# PulpPad.net
KiCad netlist of a schematic drawn in EAGLE
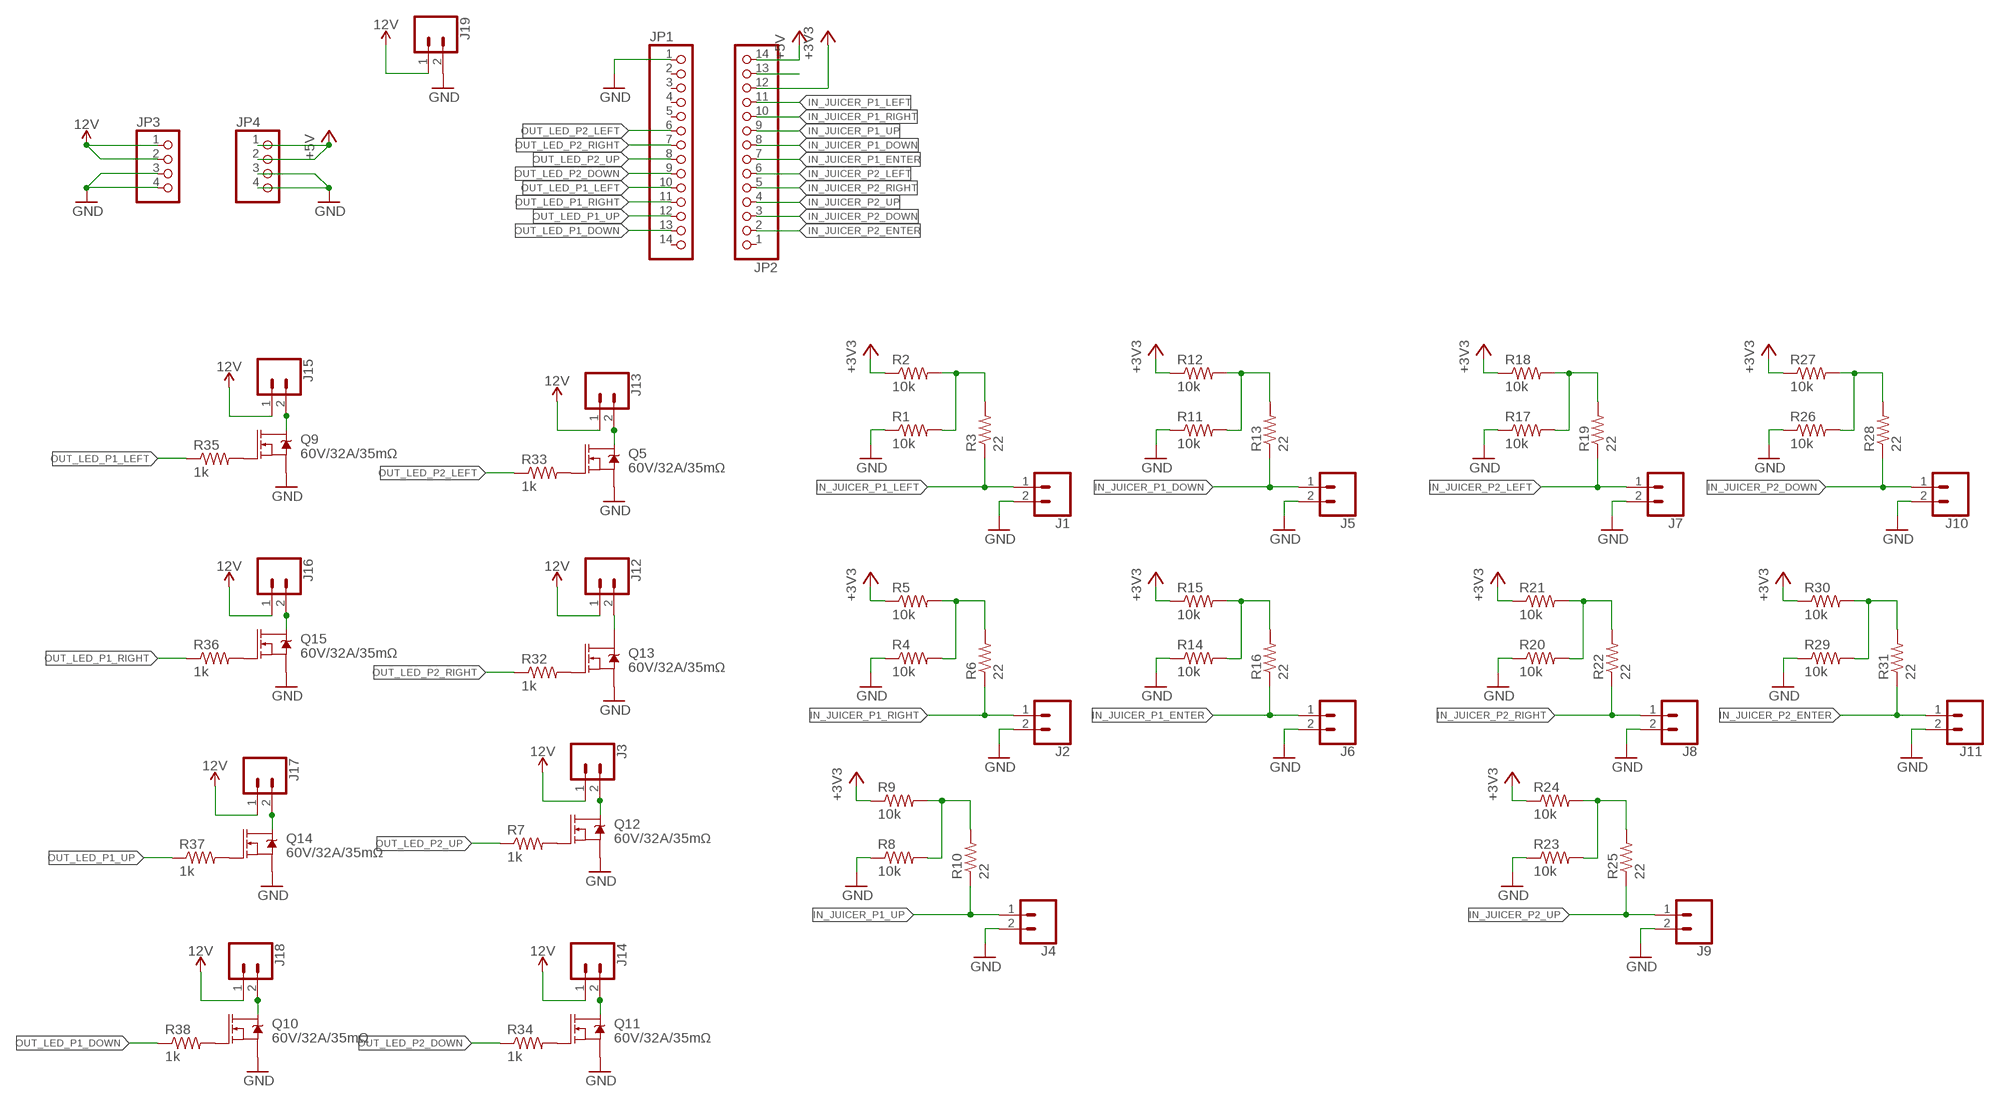
[diagram p0: schematic, sheet 1]

(export (version "E")
  (design (tool "Eeschema 10.0.6"))
  (components
    (comp (ref "J1")
      (value "CONN_023.5MM")
      (footprint "eagle-import:SCREWTERMINAL-3.5MM-2")
      (libsource (lib "eagle-import") (part "CONN_023.5MM"))
    )
    (comp (ref "J2")
      (value "CONN_023.5MM")
      (footprint "eagle-import:SCREWTERMINAL-3.5MM-2")
      (libsource (lib "eagle-import") (part "CONN_023.5MM"))
    )
    (comp (ref "J3")
      (value "CONN_023.5MM")
      (footprint "eagle-import:SCREWTERMINAL-3.5MM-2")
      (libsource (lib "eagle-import") (part "CONN_023.5MM"))
    )
    (comp (ref "J4")
      (value "CONN_023.5MM")
      (footprint "eagle-import:SCREWTERMINAL-3.5MM-2")
      (libsource (lib "eagle-import") (part "CONN_023.5MM"))
    )
    (comp (ref "J5")
      (value "CONN_023.5MM")
      (footprint "eagle-import:SCREWTERMINAL-3.5MM-2")
      (libsource (lib "eagle-import") (part "CONN_023.5MM"))
    )
    (comp (ref "J6")
      (value "CONN_023.5MM")
      (footprint "eagle-import:SCREWTERMINAL-3.5MM-2")
      (libsource (lib "eagle-import") (part "CONN_023.5MM"))
    )
    (comp (ref "J7")
      (value "CONN_023.5MM")
      (footprint "eagle-import:SCREWTERMINAL-3.5MM-2")
      (libsource (lib "eagle-import") (part "CONN_023.5MM"))
    )
    (comp (ref "J8")
      (value "CONN_023.5MM")
      (footprint "eagle-import:SCREWTERMINAL-3.5MM-2")
      (libsource (lib "eagle-import") (part "CONN_023.5MM"))
    )
    (comp (ref "J9")
      (value "CONN_023.5MM")
      (footprint "eagle-import:SCREWTERMINAL-3.5MM-2")
      (libsource (lib "eagle-import") (part "CONN_023.5MM"))
    )
    (comp (ref "J10")
      (value "CONN_023.5MM")
      (footprint "eagle-import:SCREWTERMINAL-3.5MM-2")
      (libsource (lib "eagle-import") (part "CONN_023.5MM"))
    )
    (comp (ref "J11")
      (value "CONN_023.5MM")
      (footprint "eagle-import:SCREWTERMINAL-3.5MM-2")
      (libsource (lib "eagle-import") (part "CONN_023.5MM"))
    )
    (comp (ref "J12")
      (value "CONN_023.5MM")
      (footprint "eagle-import:SCREWTERMINAL-3.5MM-2")
      (libsource (lib "eagle-import") (part "CONN_023.5MM"))
    )
    (comp (ref "J13")
      (value "CONN_023.5MM")
      (footprint "eagle-import:SCREWTERMINAL-3.5MM-2")
      (libsource (lib "eagle-import") (part "CONN_023.5MM"))
    )
    (comp (ref "J14")
      (value "CONN_023.5MM")
      (footprint "eagle-import:SCREWTERMINAL-3.5MM-2")
      (libsource (lib "eagle-import") (part "CONN_023.5MM"))
    )
    (comp (ref "J15")
      (value "CONN_023.5MM")
      (footprint "eagle-import:SCREWTERMINAL-3.5MM-2")
      (libsource (lib "eagle-import") (part "CONN_023.5MM"))
    )
    (comp (ref "J16")
      (value "CONN_023.5MM")
      (footprint "eagle-import:SCREWTERMINAL-3.5MM-2")
      (libsource (lib "eagle-import") (part "CONN_023.5MM"))
    )
    (comp (ref "J17")
      (value "CONN_023.5MM")
      (footprint "eagle-import:SCREWTERMINAL-3.5MM-2")
      (libsource (lib "eagle-import") (part "CONN_023.5MM"))
    )
    (comp (ref "J18")
      (value "CONN_023.5MM")
      (footprint "eagle-import:SCREWTERMINAL-3.5MM-2")
      (libsource (lib "eagle-import") (part "CONN_023.5MM"))
    )
    (comp (ref "J19")
      (value "CONN_023.5MM")
      (footprint "eagle-import:SCREWTERMINAL-3.5MM-2")
      (libsource (lib "eagle-import") (part "CONN_023.5MM"))
    )
    (comp (ref "JP1")
      (value "PINHD-1X14")
      (footprint "eagle-import:1X14")
      (libsource (lib "eagle-import") (part "PINHD-1X14"))
    )
    (comp (ref "JP2")
      (value "PINHD-1X14")
      (footprint "eagle-import:1X14")
      (libsource (lib "eagle-import") (part "PINHD-1X14"))
    )
    (comp (ref "JP3")
      (value "PINHD-1X4")
      (footprint "eagle-import:1X04")
      (libsource (lib "eagle-import") (part "PINHD-1X4"))
    )
    (comp (ref "JP4")
      (value "PINHD-1X4")
      (footprint "eagle-import:1X04")
      (libsource (lib "eagle-import") (part "PINHD-1X4"))
    )
    (comp (ref "Q5")
      (value "60V/32A/35mΩ")
      (footprint "eagle-import:TO220V")
      (libsource (lib "eagle-import") (part "MOSFET-NCH-FQP30N06L"))
    )
    (comp (ref "Q9")
      (value "60V/32A/35mΩ")
      (footprint "eagle-import:TO220V")
      (libsource (lib "eagle-import") (part "MOSFET-NCH-FQP30N06L"))
    )
    (comp (ref "Q10")
      (value "60V/32A/35mΩ")
      (footprint "eagle-import:TO220V")
      (libsource (lib "eagle-import") (part "MOSFET-NCH-FQP30N06L"))
    )
    (comp (ref "Q11")
      (value "60V/32A/35mΩ")
      (footprint "eagle-import:TO220V")
      (libsource (lib "eagle-import") (part "MOSFET-NCH-FQP30N06L"))
    )
    (comp (ref "Q12")
      (value "60V/32A/35mΩ")
      (footprint "eagle-import:TO220V")
      (libsource (lib "eagle-import") (part "MOSFET-NCH-FQP30N06L"))
    )
    (comp (ref "Q13")
      (value "60V/32A/35mΩ")
      (footprint "eagle-import:TO220V")
      (libsource (lib "eagle-import") (part "MOSFET-NCH-FQP30N06L"))
    )
    (comp (ref "Q14")
      (value "60V/32A/35mΩ")
      (footprint "eagle-import:TO220V")
      (libsource (lib "eagle-import") (part "MOSFET-NCH-FQP30N06L"))
    )
    (comp (ref "Q15")
      (value "60V/32A/35mΩ")
      (footprint "eagle-import:TO220V")
      (libsource (lib "eagle-import") (part "MOSFET-NCH-FQP30N06L"))
    )
    (comp (ref "R1")
      (value "10k")
      (footprint "eagle-import:0204_7")
      (libsource (lib "eagle-import") (part "R-US_0204/7"))
    )
    (comp (ref "R2")
      (value "10k")
      (footprint "eagle-import:0204_7")
      (libsource (lib "eagle-import") (part "R-US_0204/7"))
    )
    (comp (ref "R3")
      (value "22")
      (footprint "eagle-import:0204_7")
      (libsource (lib "eagle-import") (part "R-US_0204/7"))
    )
    (comp (ref "R4")
      (value "10k")
      (footprint "eagle-import:0204_7")
      (libsource (lib "eagle-import") (part "R-US_0204/7"))
    )
    (comp (ref "R5")
      (value "10k")
      (footprint "eagle-import:0204_7")
      (libsource (lib "eagle-import") (part "R-US_0204/7"))
    )
    (comp (ref "R6")
      (value "22")
      (footprint "eagle-import:0204_7")
      (libsource (lib "eagle-import") (part "R-US_0204/7"))
    )
    (comp (ref "R7")
      (value "1k")
      (footprint "eagle-import:0204_7")
      (libsource (lib "eagle-import") (part "R-US_0204/7"))
    )
    (comp (ref "R8")
      (value "10k")
      (footprint "eagle-import:0204_7")
      (libsource (lib "eagle-import") (part "R-US_0204/7"))
    )
    (comp (ref "R9")
      (value "10k")
      (footprint "eagle-import:0204_7")
      (libsource (lib "eagle-import") (part "R-US_0204/7"))
    )
    (comp (ref "R10")
      (value "22")
      (footprint "eagle-import:0204_7")
      (libsource (lib "eagle-import") (part "R-US_0204/7"))
    )
    (comp (ref "R11")
      (value "10k")
      (footprint "eagle-import:0204_7")
      (libsource (lib "eagle-import") (part "R-US_0204/7"))
    )
    (comp (ref "R12")
      (value "10k")
      (footprint "eagle-import:0204_7")
      (libsource (lib "eagle-import") (part "R-US_0204/7"))
    )
    (comp (ref "R13")
      (value "22")
      (footprint "eagle-import:0204_7")
      (libsource (lib "eagle-import") (part "R-US_0204/7"))
    )
    (comp (ref "R14")
      (value "10k")
      (footprint "eagle-import:0204_7")
      (libsource (lib "eagle-import") (part "R-US_0204/7"))
    )
    (comp (ref "R15")
      (value "10k")
      (footprint "eagle-import:0204_7")
      (libsource (lib "eagle-import") (part "R-US_0204/7"))
    )
    (comp (ref "R16")
      (value "22")
      (footprint "eagle-import:0204_7")
      (libsource (lib "eagle-import") (part "R-US_0204/7"))
    )
    (comp (ref "R17")
      (value "10k")
      (footprint "eagle-import:0204_7")
      (libsource (lib "eagle-import") (part "R-US_0204/7"))
    )
    (comp (ref "R18")
      (value "10k")
      (footprint "eagle-import:0204_7")
      (libsource (lib "eagle-import") (part "R-US_0204/7"))
    )
    (comp (ref "R19")
      (value "22")
      (footprint "eagle-import:0204_7")
      (libsource (lib "eagle-import") (part "R-US_0204/7"))
    )
    (comp (ref "R20")
      (value "10k")
      (footprint "eagle-import:0204_7")
      (libsource (lib "eagle-import") (part "R-US_0204/7"))
    )
    (comp (ref "R21")
      (value "10k")
      (footprint "eagle-import:0204_7")
      (libsource (lib "eagle-import") (part "R-US_0204/7"))
    )
    (comp (ref "R22")
      (value "22")
      (footprint "eagle-import:0204_7")
      (libsource (lib "eagle-import") (part "R-US_0204/7"))
    )
    (comp (ref "R23")
      (value "10k")
      (footprint "eagle-import:0204_7")
      (libsource (lib "eagle-import") (part "R-US_0204/7"))
    )
    (comp (ref "R24")
      (value "10k")
      (footprint "eagle-import:0204_7")
      (libsource (lib "eagle-import") (part "R-US_0204/7"))
    )
    (comp (ref "R25")
      (value "22")
      (footprint "eagle-import:0204_7")
      (libsource (lib "eagle-import") (part "R-US_0204/7"))
    )
    (comp (ref "R26")
      (value "10k")
      (footprint "eagle-import:0204_7")
      (libsource (lib "eagle-import") (part "R-US_0204/7"))
    )
    (comp (ref "R27")
      (value "10k")
      (footprint "eagle-import:0204_7")
      (libsource (lib "eagle-import") (part "R-US_0204/7"))
    )
    (comp (ref "R28")
      (value "22")
      (footprint "eagle-import:0204_7")
      (libsource (lib "eagle-import") (part "R-US_0204/7"))
    )
    (comp (ref "R29")
      (value "10k")
      (footprint "eagle-import:0204_7")
      (libsource (lib "eagle-import") (part "R-US_0204/7"))
    )
    (comp (ref "R30")
      (value "10k")
      (footprint "eagle-import:0204_7")
      (libsource (lib "eagle-import") (part "R-US_0204/7"))
    )
    (comp (ref "R31")
      (value "22")
      (footprint "eagle-import:0204_7")
      (libsource (lib "eagle-import") (part "R-US_0204/7"))
    )
    (comp (ref "R32")
      (value "1k")
      (footprint "eagle-import:0204_7")
      (libsource (lib "eagle-import") (part "R-US_0204/7"))
    )
    (comp (ref "R33")
      (value "1k")
      (footprint "eagle-import:0204_7")
      (libsource (lib "eagle-import") (part "R-US_0204/7"))
    )
    (comp (ref "R34")
      (value "1k")
      (footprint "eagle-import:0204_7")
      (libsource (lib "eagle-import") (part "R-US_0204/7"))
    )
    (comp (ref "R35")
      (value "1k")
      (footprint "eagle-import:0204_7")
      (libsource (lib "eagle-import") (part "R-US_0204/7"))
    )
    (comp (ref "R36")
      (value "1k")
      (footprint "eagle-import:0204_7")
      (libsource (lib "eagle-import") (part "R-US_0204/7"))
    )
    (comp (ref "R37")
      (value "1k")
      (footprint "eagle-import:0204_7")
      (libsource (lib "eagle-import") (part "R-US_0204/7"))
    )
    (comp (ref "R38")
      (value "1k")
      (footprint "eagle-import:0204_7")
      (libsource (lib "eagle-import") (part "R-US_0204/7"))
    )
  )
  (nets
    (net (code "1") (name "+3V3") (class "Default")
      (node (ref "JP2") (pin "12") (pinfunction "12_12") (pintype "passive"))
      (node (ref "R12") (pin "1") (pinfunction "1_1") (pintype "passive"))
      (node (ref "R15") (pin "1") (pinfunction "1_1") (pintype "passive"))
      (node (ref "R18") (pin "1") (pinfunction "1_1") (pintype "passive"))
      (node (ref "R2") (pin "1") (pinfunction "1_1") (pintype "passive"))
      (node (ref "R21") (pin "1") (pinfunction "1_1") (pintype "passive"))
      (node (ref "R24") (pin "1") (pinfunction "1_1") (pintype "passive"))
      (node (ref "R27") (pin "1") (pinfunction "1_1") (pintype "passive"))
      (node (ref "R30") (pin "1") (pinfunction "1_1") (pintype "passive"))
      (node (ref "R5") (pin "1") (pinfunction "1_1") (pintype "passive"))
      (node (ref "R9") (pin "1") (pinfunction "1_1") (pintype "passive"))
    )
    (net (code "2") (name "+5V") (class "Default")
      (node (ref "JP2") (pin "14") (pinfunction "14_14") (pintype "passive"))
      (node (ref "JP4") (pin "1") (pinfunction "1_1") (pintype "passive"))
      (node (ref "JP4") (pin "2") (pinfunction "2_2") (pintype "passive"))
    )
    (net (code "3") (name "12V") (class "Default")
      (node (ref "J12") (pin "1") (pinfunction "1_1") (pintype "passive"))
      (node (ref "J13") (pin "1") (pinfunction "1_1") (pintype "passive"))
      (node (ref "J14") (pin "1") (pinfunction "1_1") (pintype "passive"))
      (node (ref "J15") (pin "1") (pinfunction "1_1") (pintype "passive"))
      (node (ref "J16") (pin "1") (pinfunction "1_1") (pintype "passive"))
      (node (ref "J17") (pin "1") (pinfunction "1_1") (pintype "passive"))
      (node (ref "J18") (pin "1") (pinfunction "1_1") (pintype "passive"))
      (node (ref "J19") (pin "1") (pinfunction "1_1") (pintype "passive"))
      (node (ref "J3") (pin "1") (pinfunction "1_1") (pintype "passive"))
      (node (ref "JP3") (pin "1") (pinfunction "1_1") (pintype "passive"))
      (node (ref "JP3") (pin "2") (pinfunction "2_2") (pintype "passive"))
    )
    (net (code "4") (name "GND") (class "Default")
      (node (ref "J1") (pin "2") (pinfunction "2_2") (pintype "passive"))
      (node (ref "J10") (pin "2") (pinfunction "2_2") (pintype "passive"))
      (node (ref "J11") (pin "2") (pinfunction "2_2") (pintype "passive"))
      (node (ref "J19") (pin "2") (pinfunction "2_2") (pintype "passive"))
      (node (ref "J2") (pin "2") (pinfunction "2_2") (pintype "passive"))
      (node (ref "J4") (pin "2") (pinfunction "2_2") (pintype "passive"))
      (node (ref "J5") (pin "2") (pinfunction "2_2") (pintype "passive"))
      (node (ref "J6") (pin "2") (pinfunction "2_2") (pintype "passive"))
      (node (ref "J7") (pin "2") (pinfunction "2_2") (pintype "passive"))
      (node (ref "J8") (pin "2") (pinfunction "2_2") (pintype "passive"))
      (node (ref "J9") (pin "2") (pinfunction "2_2") (pintype "passive"))
      (node (ref "JP1") (pin "1") (pinfunction "1_1") (pintype "passive"))
      (node (ref "JP3") (pin "3") (pinfunction "3_3") (pintype "passive"))
      (node (ref "JP3") (pin "4") (pinfunction "4_4") (pintype "passive"))
      (node (ref "JP4") (pin "3") (pinfunction "3_3") (pintype "passive"))
      (node (ref "JP4") (pin "4") (pinfunction "4_4") (pintype "passive"))
      (node (ref "Q10") (pin "3") (pinfunction "S_3") (pintype "bidirectional"))
      (node (ref "Q11") (pin "3") (pinfunction "S_3") (pintype "bidirectional"))
      (node (ref "Q12") (pin "3") (pinfunction "S_3") (pintype "bidirectional"))
      (node (ref "Q13") (pin "3") (pinfunction "S_3") (pintype "bidirectional"))
      (node (ref "Q14") (pin "3") (pinfunction "S_3") (pintype "bidirectional"))
      (node (ref "Q15") (pin "3") (pinfunction "S_3") (pintype "bidirectional"))
      (node (ref "Q5") (pin "3") (pinfunction "S_3") (pintype "bidirectional"))
      (node (ref "Q9") (pin "3") (pinfunction "S_3") (pintype "bidirectional"))
      (node (ref "R1") (pin "1") (pinfunction "1_1") (pintype "passive"))
      (node (ref "R11") (pin "1") (pinfunction "1_1") (pintype "passive"))
      (node (ref "R14") (pin "1") (pinfunction "1_1") (pintype "passive"))
      (node (ref "R17") (pin "1") (pinfunction "1_1") (pintype "passive"))
      (node (ref "R20") (pin "1") (pinfunction "1_1") (pintype "passive"))
      (node (ref "R23") (pin "1") (pinfunction "1_1") (pintype "passive"))
      (node (ref "R26") (pin "1") (pinfunction "1_1") (pintype "passive"))
      (node (ref "R29") (pin "1") (pinfunction "1_1") (pintype "passive"))
      (node (ref "R4") (pin "1") (pinfunction "1_1") (pintype "passive"))
      (node (ref "R8") (pin "1") (pinfunction "1_1") (pintype "passive"))
    )
    (net (code "5") (name "IN_JUICER_P1_DOWN") (class "Default")
      (node (ref "J5") (pin "1") (pinfunction "1_1") (pintype "passive"))
      (node (ref "JP2") (pin "8") (pinfunction "8_8") (pintype "passive"))
      (node (ref "R13") (pin "1") (pinfunction "1_1") (pintype "passive"))
    )
    (net (code "6") (name "IN_JUICER_P1_ENTER") (class "Default")
      (node (ref "J6") (pin "1") (pinfunction "1_1") (pintype "passive"))
      (node (ref "JP2") (pin "7") (pinfunction "7_7") (pintype "passive"))
      (node (ref "R16") (pin "1") (pinfunction "1_1") (pintype "passive"))
    )
    (net (code "7") (name "IN_JUICER_P1_LEFT") (class "Default")
      (node (ref "J1") (pin "1") (pinfunction "1_1") (pintype "passive"))
      (node (ref "JP2") (pin "11") (pinfunction "11_11") (pintype "passive"))
      (node (ref "R3") (pin "1") (pinfunction "1_1") (pintype "passive"))
    )
    (net (code "8") (name "IN_JUICER_P1_RIGHT") (class "Default")
      (node (ref "J2") (pin "1") (pinfunction "1_1") (pintype "passive"))
      (node (ref "JP2") (pin "10") (pinfunction "10_10") (pintype "passive"))
      (node (ref "R6") (pin "1") (pinfunction "1_1") (pintype "passive"))
    )
    (net (code "9") (name "IN_JUICER_P1_UP") (class "Default")
      (node (ref "J4") (pin "1") (pinfunction "1_1") (pintype "passive"))
      (node (ref "JP2") (pin "9") (pinfunction "9_9") (pintype "passive"))
      (node (ref "R10") (pin "1") (pinfunction "1_1") (pintype "passive"))
    )
    (net (code "10") (name "IN_JUICER_P2_DOWN") (class "Default")
      (node (ref "J10") (pin "1") (pinfunction "1_1") (pintype "passive"))
      (node (ref "JP2") (pin "3") (pinfunction "3_3") (pintype "passive"))
      (node (ref "R28") (pin "1") (pinfunction "1_1") (pintype "passive"))
    )
    (net (code "11") (name "IN_JUICER_P2_ENTER") (class "Default")
      (node (ref "J11") (pin "1") (pinfunction "1_1") (pintype "passive"))
      (node (ref "JP2") (pin "2") (pinfunction "2_2") (pintype "passive"))
      (node (ref "R31") (pin "1") (pinfunction "1_1") (pintype "passive"))
    )
    (net (code "12") (name "IN_JUICER_P2_LEFT") (class "Default")
      (node (ref "J7") (pin "1") (pinfunction "1_1") (pintype "passive"))
      (node (ref "JP2") (pin "6") (pinfunction "6_6") (pintype "passive"))
      (node (ref "R19") (pin "1") (pinfunction "1_1") (pintype "passive"))
    )
    (net (code "13") (name "IN_JUICER_P2_RIGHT") (class "Default")
      (node (ref "J8") (pin "1") (pinfunction "1_1") (pintype "passive"))
      (node (ref "JP2") (pin "5") (pinfunction "5_5") (pintype "passive"))
      (node (ref "R22") (pin "1") (pinfunction "1_1") (pintype "passive"))
    )
    (net (code "14") (name "IN_JUICER_P2_UP") (class "Default")
      (node (ref "J9") (pin "1") (pinfunction "1_1") (pintype "passive"))
      (node (ref "JP2") (pin "4") (pinfunction "4_4") (pintype "passive"))
      (node (ref "R25") (pin "1") (pinfunction "1_1") (pintype "passive"))
    )
    (net (code "15") (name "Net-(Q5-D)") (class "Default")
      (node (ref "J13") (pin "2") (pinfunction "2_2") (pintype "passive"))
      (node (ref "Q5") (pin "2") (pinfunction "D_2") (pintype "bidirectional"))
    )
    (net (code "16") (name "Net-(Q5-G)") (class "Default")
      (node (ref "Q5") (pin "1") (pinfunction "G_1") (pintype "bidirectional"))
      (node (ref "R33") (pin "2") (pinfunction "2_2") (pintype "passive"))
    )
    (net (code "17") (name "Net-(Q9-D)") (class "Default")
      (node (ref "J15") (pin "2") (pinfunction "2_2") (pintype "passive"))
      (node (ref "Q9") (pin "2") (pinfunction "D_2") (pintype "bidirectional"))
    )
    (net (code "18") (name "Net-(Q9-G)") (class "Default")
      (node (ref "Q9") (pin "1") (pinfunction "G_1") (pintype "bidirectional"))
      (node (ref "R35") (pin "2") (pinfunction "2_2") (pintype "passive"))
    )
    (net (code "19") (name "Net-(Q10-D)") (class "Default")
      (node (ref "J18") (pin "2") (pinfunction "2_2") (pintype "passive"))
      (node (ref "Q10") (pin "2") (pinfunction "D_2") (pintype "bidirectional"))
    )
    (net (code "20") (name "Net-(Q10-G)") (class "Default")
      (node (ref "Q10") (pin "1") (pinfunction "G_1") (pintype "bidirectional"))
      (node (ref "R38") (pin "2") (pinfunction "2_2") (pintype "passive"))
    )
    (net (code "21") (name "Net-(Q11-D)") (class "Default")
      (node (ref "J14") (pin "2") (pinfunction "2_2") (pintype "passive"))
      (node (ref "Q11") (pin "2") (pinfunction "D_2") (pintype "bidirectional"))
    )
    (net (code "22") (name "Net-(Q11-G)") (class "Default")
      (node (ref "Q11") (pin "1") (pinfunction "G_1") (pintype "bidirectional"))
      (node (ref "R34") (pin "2") (pinfunction "2_2") (pintype "passive"))
    )
    (net (code "23") (name "Net-(Q12-D)") (class "Default")
      (node (ref "J3") (pin "2") (pinfunction "2_2") (pintype "passive"))
      (node (ref "Q12") (pin "2") (pinfunction "D_2") (pintype "bidirectional"))
    )
    (net (code "24") (name "Net-(Q12-G)") (class "Default")
      (node (ref "Q12") (pin "1") (pinfunction "G_1") (pintype "bidirectional"))
      (node (ref "R7") (pin "2") (pinfunction "2_2") (pintype "passive"))
    )
    (net (code "25") (name "Net-(Q13-D)") (class "Default")
      (node (ref "J12") (pin "2") (pinfunction "2_2") (pintype "passive"))
      (node (ref "Q13") (pin "2") (pinfunction "D_2") (pintype "bidirectional"))
    )
    (net (code "26") (name "Net-(Q13-G)") (class "Default")
      (node (ref "Q13") (pin "1") (pinfunction "G_1") (pintype "bidirectional"))
      (node (ref "R32") (pin "2") (pinfunction "2_2") (pintype "passive"))
    )
    (net (code "27") (name "Net-(Q14-D)") (class "Default")
      (node (ref "J17") (pin "2") (pinfunction "2_2") (pintype "passive"))
      (node (ref "Q14") (pin "2") (pinfunction "D_2") (pintype "bidirectional"))
    )
    (net (code "28") (name "Net-(Q14-G)") (class "Default")
      (node (ref "Q14") (pin "1") (pinfunction "G_1") (pintype "bidirectional"))
      (node (ref "R37") (pin "2") (pinfunction "2_2") (pintype "passive"))
    )
    (net (code "29") (name "Net-(Q15-D)") (class "Default")
      (node (ref "J16") (pin "2") (pinfunction "2_2") (pintype "passive"))
      (node (ref "Q15") (pin "2") (pinfunction "D_2") (pintype "bidirectional"))
    )
    (net (code "30") (name "Net-(Q15-G)") (class "Default")
      (node (ref "Q15") (pin "1") (pinfunction "G_1") (pintype "bidirectional"))
      (node (ref "R36") (pin "2") (pinfunction "2_2") (pintype "passive"))
    )
    (net (code "31") (name "Net-(R1-Pad2)") (class "Default")
      (node (ref "R1") (pin "2") (pinfunction "2_2") (pintype "passive"))
      (node (ref "R2") (pin "2") (pinfunction "2_2") (pintype "passive"))
      (node (ref "R3") (pin "2") (pinfunction "2_2") (pintype "passive"))
    )
    (net (code "32") (name "Net-(R4-Pad2)") (class "Default")
      (node (ref "R4") (pin "2") (pinfunction "2_2") (pintype "passive"))
      (node (ref "R5") (pin "2") (pinfunction "2_2") (pintype "passive"))
      (node (ref "R6") (pin "2") (pinfunction "2_2") (pintype "passive"))
    )
    (net (code "33") (name "Net-(R10-Pad2)") (class "Default")
      (node (ref "R10") (pin "2") (pinfunction "2_2") (pintype "passive"))
      (node (ref "R8") (pin "2") (pinfunction "2_2") (pintype "passive"))
      (node (ref "R9") (pin "2") (pinfunction "2_2") (pintype "passive"))
    )
    (net (code "34") (name "Net-(R11-Pad2)") (class "Default")
      (node (ref "R11") (pin "2") (pinfunction "2_2") (pintype "passive"))
      (node (ref "R12") (pin "2") (pinfunction "2_2") (pintype "passive"))
      (node (ref "R13") (pin "2") (pinfunction "2_2") (pintype "passive"))
    )
    (net (code "35") (name "Net-(R14-Pad2)") (class "Default")
      (node (ref "R14") (pin "2") (pinfunction "2_2") (pintype "passive"))
      (node (ref "R15") (pin "2") (pinfunction "2_2") (pintype "passive"))
      (node (ref "R16") (pin "2") (pinfunction "2_2") (pintype "passive"))
    )
    (net (code "36") (name "Net-(R17-Pad2)") (class "Default")
      (node (ref "R17") (pin "2") (pinfunction "2_2") (pintype "passive"))
      (node (ref "R18") (pin "2") (pinfunction "2_2") (pintype "passive"))
      (node (ref "R19") (pin "2") (pinfunction "2_2") (pintype "passive"))
    )
    (net (code "37") (name "Net-(R20-Pad2)") (class "Default")
      (node (ref "R20") (pin "2") (pinfunction "2_2") (pintype "passive"))
      (node (ref "R21") (pin "2") (pinfunction "2_2") (pintype "passive"))
      (node (ref "R22") (pin "2") (pinfunction "2_2") (pintype "passive"))
    )
    (net (code "38") (name "Net-(R23-Pad2)") (class "Default")
      (node (ref "R23") (pin "2") (pinfunction "2_2") (pintype "passive"))
      (node (ref "R24") (pin "2") (pinfunction "2_2") (pintype "passive"))
      (node (ref "R25") (pin "2") (pinfunction "2_2") (pintype "passive"))
    )
    (net (code "39") (name "Net-(R26-Pad2)") (class "Default")
      (node (ref "R26") (pin "2") (pinfunction "2_2") (pintype "passive"))
      (node (ref "R27") (pin "2") (pinfunction "2_2") (pintype "passive"))
      (node (ref "R28") (pin "2") (pinfunction "2_2") (pintype "passive"))
    )
    (net (code "40") (name "Net-(R29-Pad2)") (class "Default")
      (node (ref "R29") (pin "2") (pinfunction "2_2") (pintype "passive"))
      (node (ref "R30") (pin "2") (pinfunction "2_2") (pintype "passive"))
      (node (ref "R31") (pin "2") (pinfunction "2_2") (pintype "passive"))
    )
    (net (code "41") (name "OUT_LED_P1_DOWN") (class "Default")
      (node (ref "JP1") (pin "13") (pinfunction "13_13") (pintype "passive"))
      (node (ref "R38") (pin "1") (pinfunction "1_1") (pintype "passive"))
    )
    (net (code "42") (name "OUT_LED_P1_LEFT") (class "Default")
      (node (ref "JP1") (pin "10") (pinfunction "10_10") (pintype "passive"))
      (node (ref "R35") (pin "1") (pinfunction "1_1") (pintype "passive"))
    )
    (net (code "43") (name "OUT_LED_P1_RIGHT") (class "Default")
      (node (ref "JP1") (pin "11") (pinfunction "11_11") (pintype "passive"))
      (node (ref "R36") (pin "1") (pinfunction "1_1") (pintype "passive"))
    )
    (net (code "44") (name "OUT_LED_P1_UP") (class "Default")
      (node (ref "JP1") (pin "12") (pinfunction "12_12") (pintype "passive"))
      (node (ref "R37") (pin "1") (pinfunction "1_1") (pintype "passive"))
    )
    (net (code "45") (name "OUT_LED_P2_DOWN") (class "Default")
      (node (ref "JP1") (pin "9") (pinfunction "9_9") (pintype "passive"))
      (node (ref "R34") (pin "1") (pinfunction "1_1") (pintype "passive"))
    )
    (net (code "46") (name "OUT_LED_P2_LEFT") (class "Default")
      (node (ref "JP1") (pin "6") (pinfunction "6_6") (pintype "passive"))
      (node (ref "R33") (pin "1") (pinfunction "1_1") (pintype "passive"))
    )
    (net (code "47") (name "OUT_LED_P2_RIGHT") (class "Default")
      (node (ref "JP1") (pin "7") (pinfunction "7_7") (pintype "passive"))
      (node (ref "R32") (pin "1") (pinfunction "1_1") (pintype "passive"))
    )
    (net (code "48") (name "OUT_LED_P2_UP") (class "Default")
      (node (ref "JP1") (pin "8") (pinfunction "8_8") (pintype "passive"))
      (node (ref "R7") (pin "1") (pinfunction "1_1") (pintype "passive"))
    )
    (net (code "49") (name "unconnected-(JP1-Pad2)") (class "Default")
      (node (ref "JP1") (pin "2") (pinfunction "2_2") (pintype "passive"))
    )
    (net (code "50") (name "unconnected-(JP1-Pad3)") (class "Default")
      (node (ref "JP1") (pin "3") (pinfunction "3_3") (pintype "passive"))
    )
    (net (code "51") (name "unconnected-(JP1-Pad4)") (class "Default")
      (node (ref "JP1") (pin "4") (pinfunction "4_4") (pintype "passive"))
    )
    (net (code "52") (name "unconnected-(JP1-Pad5)") (class "Default")
      (node (ref "JP1") (pin "5") (pinfunction "5_5") (pintype "passive"))
    )
    (net (code "53") (name "unconnected-(JP1-Pad14)") (class "Default")
      (node (ref "JP1") (pin "14") (pinfunction "14_14") (pintype "passive"))
    )
    (net (code "54") (name "unconnected-(JP2-Pad1)") (class "Default")
      (node (ref "JP2") (pin "1") (pinfunction "1_1") (pintype "passive"))
    )
    (net (code "55") (name "unconnected-(JP2-Pad13)") (class "Default")
      (node (ref "JP2") (pin "13") (pinfunction "13_13") (pintype "passive"))
    )
  )
)
